# OutputAmplifier.net
KiCad netlist of a schematic drawn in Altium Designer
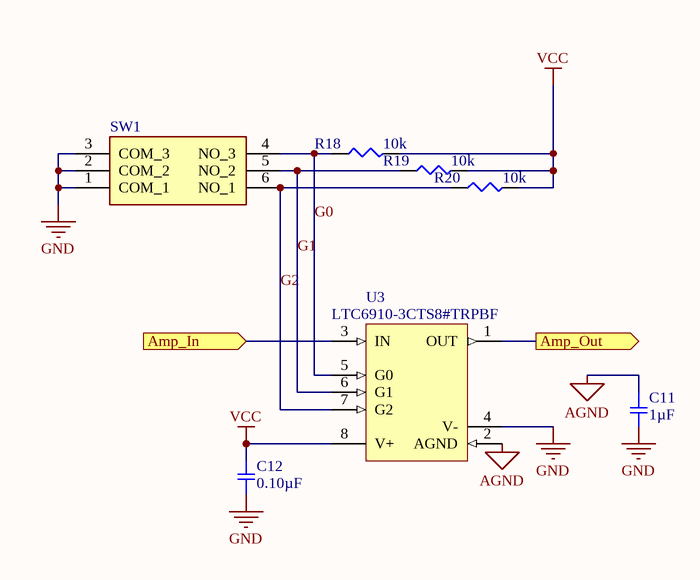
[diagram p0: OutputAmplifier.SchDoc]

(export (version "E")
  (design (tool "Eeschema 10.0.6"))
  (components
    (comp (ref "C11")
      (value "1µF")
      (footprint "SMD-0603C")
      (description "CAP CER 1UF 16V X7R 0603")
      (fields
        (field (name "DIGI-KEY PART NUMBER") "490-5241-1-ND")
        (field (name "PART NUMBER") "GCM188R71C105KA64D")
      )
      (libsource (lib "capacitor_murata_0603") (part "GCM188R71C105KA64D"))
    )
    (comp (ref "C12")
      (value "0.10µF")
      (footprint "SMD-0603C")
      (description "CAP CER 0.1UF 16V X7R 0603")
      (fields
        (field (name "DIGI-KEY PART NUMBER") "490-5796-1-ND")
        (field (name "PART NUMBER") "GCJ188R71C104KA01D")
      )
      (libsource (lib "capacitor_murata_0603") (part "GCJ188R71C104KA01D"))
    )
    (comp (ref "R18")
      (value "10k")
      (footprint "SMD-0603-RES")
      (description "RES SMD 10K OHM 1% 1/10W 0603")
      (fields
        (field (name "MANUFACTURER") "Panasonic Electronic Components")
        (field (name "MANUFACTURER PART NUMBER") "RNCP0603FTD10K0")
      )
      (libsource (lib "Panasonic_resistor_0603") (part "ERJ-3EKF1002V"))
    )
    (comp (ref "R19")
      (value "10k")
      (footprint "SMD-0603-RES")
      (description "RES SMD 10K OHM 1% 1/10W 0603")
      (fields
        (field (name "MANUFACTURER") "Panasonic Electronic Components")
        (field (name "MANUFACTURER PART NUMBER") "RNCP0603FTD10K0")
      )
      (libsource (lib "Panasonic_resistor_0603") (part "ERJ-3EKF1002V"))
    )
    (comp (ref "R20")
      (value "10k")
      (footprint "SMD-0603-RES")
      (description "RES SMD 10K OHM 1% 1/10W 0603")
      (fields
        (field (name "MANUFACTURER") "Panasonic Electronic Components")
        (field (name "MANUFACTURER PART NUMBER") "RNCP0603FTD10K0")
      )
      (libsource (lib "Panasonic_resistor_0603") (part "ERJ-3EKF1002V"))
    )
    (comp (ref "SW1")
      (value "416131160803")
      (footprint "416131160803")
      (description "Switch")
      (fields (field (name "MOUSER PART NUMBER") "710-416131160803"))
      (libsource (lib "URC_Lib") (part "416131160803"))
    )
    (comp (ref "U3")
      (value "LTC6910-3CTS8#TRPBF")
      (footprint "LT-TS8-8-TSOT-23_V")
      (fields
        (field (name "MANUFACTURER") "Analog Devices Inc.")
        (field (name "MANUFACTURER PART NUMBER") "LTC6910-3CTS8#TRMPBF")
      )
      (libsource (lib "Altium Content Vault") (part "LT-LTC6910-TS8-8"))
    )
  )
  (nets
    (net (code "1") (name "/Amp_In") (class "Default")
      (node (ref "U3") (pin "3") (pinfunction "IN_3") (pintype "input"))
    )
    (net (code "2") (name "/Amp_Out") (class "Default")
      (node (ref "U3") (pin "1") (pinfunction "OUT_1") (pintype "output"))
    )
    (net (code "3") (name "/G0") (class "Default")
      (node (ref "R18") (pin "1") (pinfunction "1_1") (pintype "passive"))
      (node (ref "SW1") (pin "4") (pinfunction "NO_3_4") (pintype "passive"))
      (node (ref "U3") (pin "5") (pinfunction "G0_5") (pintype "input"))
    )
    (net (code "4") (name "/G1") (class "Default")
      (node (ref "R19") (pin "1") (pinfunction "1_1") (pintype "passive"))
      (node (ref "SW1") (pin "5") (pinfunction "NO_2_5") (pintype "passive"))
      (node (ref "U3") (pin "6") (pinfunction "G1_6") (pintype "input"))
    )
    (net (code "5") (name "/G2") (class "Default")
      (node (ref "R20") (pin "1") (pinfunction "1_1") (pintype "passive"))
      (node (ref "SW1") (pin "6") (pinfunction "NO_1_6") (pintype "passive"))
      (node (ref "U3") (pin "7") (pinfunction "G2_7") (pintype "input"))
    )
    (net (code "6") (name "AGND") (class "Default")
      (node (ref "C11") (pin "1") (pinfunction "1_1") (pintype "passive"))
      (node (ref "U3") (pin "2") (pinfunction "AGND_2") (pintype "input"))
    )
    (net (code "7") (name "GND") (class "Default")
      (node (ref "C11") (pin "2") (pinfunction "2_2") (pintype "passive"))
      (node (ref "C12") (pin "1") (pinfunction "1_1") (pintype "passive"))
      (node (ref "SW1") (pin "1") (pinfunction "COM_1_1") (pintype "passive"))
      (node (ref "SW1") (pin "2") (pinfunction "COM_2_2") (pintype "passive"))
      (node (ref "SW1") (pin "3") (pinfunction "COM_3_3") (pintype "passive"))
      (node (ref "U3") (pin "4") (pinfunction "V-_4") (pintype "power_in"))
    )
    (net (code "8") (name "VCC") (class "Default")
      (node (ref "C12") (pin "2") (pinfunction "2_2") (pintype "passive"))
      (node (ref "R18") (pin "2") (pinfunction "2_2") (pintype "passive"))
      (node (ref "R19") (pin "2") (pinfunction "2_2") (pintype "passive"))
      (node (ref "R20") (pin "2") (pinfunction "2_2") (pintype "passive"))
      (node (ref "U3") (pin "8") (pinfunction "V+_8") (pintype "power_in"))
    )
  )
)
